# TJA1051T.net
KiCad netlist of a schematic drawn in Altium Designer
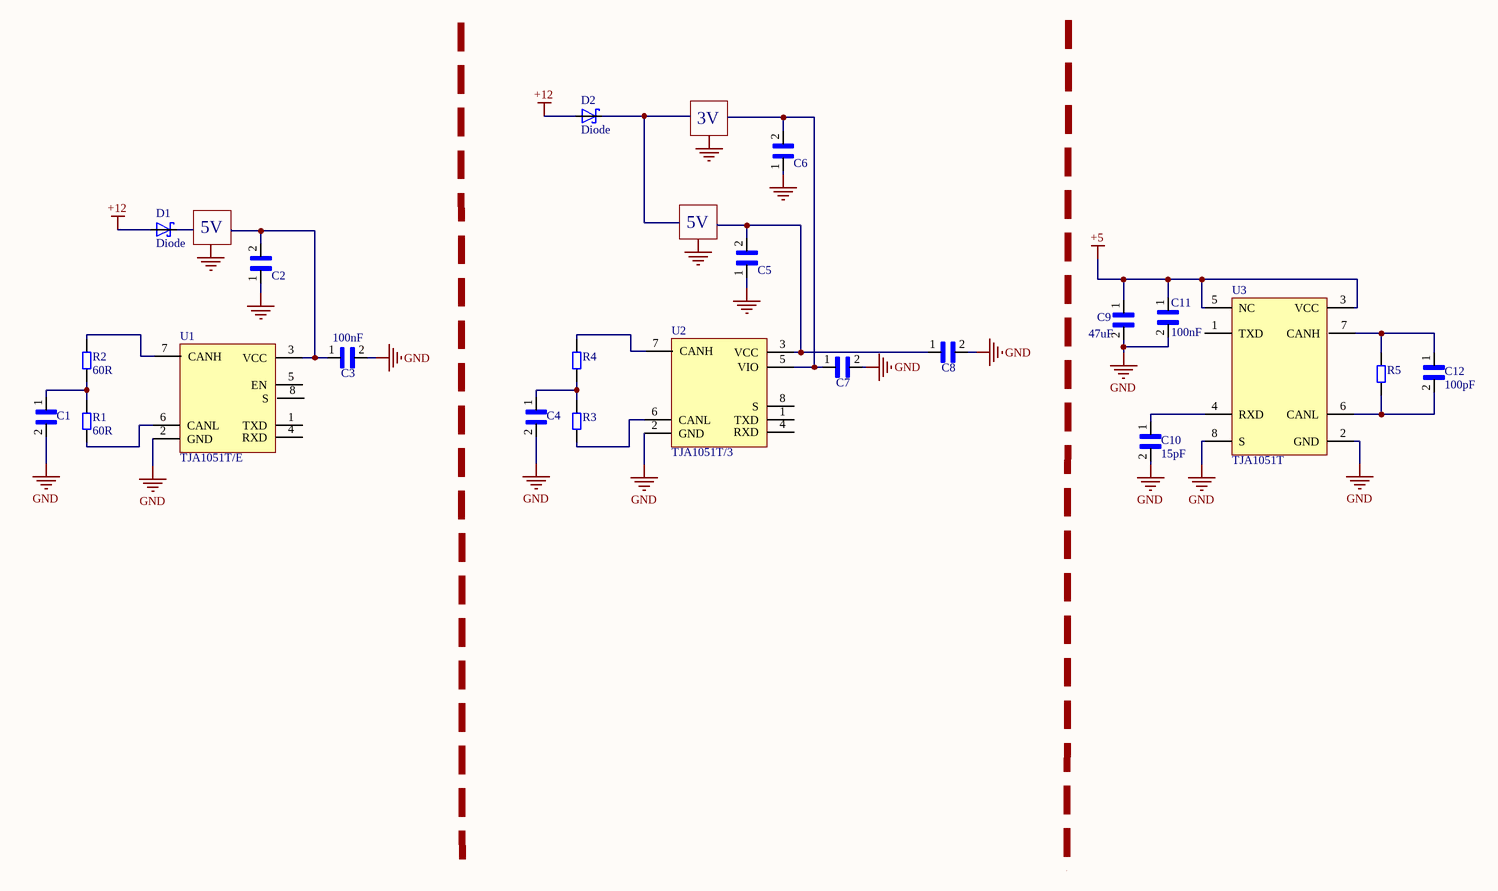
[diagram p0: TJA1051T.SchDoc]

(export (version "E")
  (design (tool "Eeschema 10.0.6"))
  (components
    (comp (ref "C1")
      (value "CAP-0805-NP0-10nF")
      (footprint "CAP-0805-NP0")
      (description "Cap Ceramic 0.01uF 50V C0G 5% Pad SMD 0805 125°C T/R")
      (fields
        (field (name "MANUFACTURER") "Yageo")
        (field (name "MANUFACTURER PART NUMBER") "CC0805JKNPO9BN103")
      )
      (libsource (lib "Schlib2") (part "CAP-0805-NP0-10nF"))
    )
    (comp (ref "C2")
      (value "CAP-0805-NP0-10nF")
      (footprint "CAP-0805-NP0")
      (description "Cap Ceramic 0.01uF 50V C0G 5% Pad SMD 0805 125°C T/R")
      (fields
        (field (name "MANUFACTURER") "Yageo")
        (field (name "MANUFACTURER PART NUMBER") "CC0805JKNPO9BN103")
      )
      (libsource (lib "") (part "CAP-0805-NP0-10nF_2"))
    )
    (comp (ref "C3")
      (value "100nF")
      (footprint "CAP-0805-NP0")
      (description "Cap Ceramic 0.01uF 50V C0G 5% Pad SMD 0805 125°C T/R")
      (fields
        (field (name "MANUFACTURER") "Yageo")
        (field (name "MANUFACTURER PART NUMBER") "CC0805JKNPO9BN103")
      )
      (libsource (lib "") (part "CAP-0805-NP0-10nF_1"))
    )
    (comp (ref "C4")
      (value "CAP-0805-NP0-10nF")
      (footprint "CAP-0805-NP0")
      (description "Cap Ceramic 0.01uF 50V C0G 5% Pad SMD 0805 125°C T/R")
      (fields
        (field (name "MANUFACTURER") "Yageo")
        (field (name "MANUFACTURER PART NUMBER") "CC0805JKNPO9BN103")
      )
      (libsource (lib "Schlib2") (part "CAP-0805-NP0-10nF"))
    )
    (comp (ref "C5")
      (value "CAP-0805-NP0-10nF")
      (footprint "CAP-0805-NP0")
      (description "Cap Ceramic 0.01uF 50V C0G 5% Pad SMD 0805 125°C T/R")
      (fields
        (field (name "MANUFACTURER") "Yageo")
        (field (name "MANUFACTURER PART NUMBER") "CC0805JKNPO9BN103")
      )
      (libsource (lib "") (part "CAP-0805-NP0-10nF_2"))
    )
    (comp (ref "C6")
      (value "CAP-0805-NP0-10nF")
      (footprint "CAP-0805-NP0")
      (description "Cap Ceramic 0.01uF 50V C0G 5% Pad SMD 0805 125°C T/R")
      (fields
        (field (name "MANUFACTURER") "Yageo")
        (field (name "MANUFACTURER PART NUMBER") "CC0805JKNPO9BN103")
      )
      (libsource (lib "") (part "CAP-0805-NP0-10nF_2"))
    )
    (comp (ref "C7")
      (value "CAP-0805-NP0-10nF")
      (footprint "CAP-0805-NP0")
      (description "Cap Ceramic 0.01uF 50V C0G 5% Pad SMD 0805 125°C T/R")
      (fields
        (field (name "MANUFACTURER") "Yageo")
        (field (name "MANUFACTURER PART NUMBER") "CC0805JKNPO9BN103")
      )
      (libsource (lib "") (part "CAP-0805-NP0-10nF_1"))
    )
    (comp (ref "C8")
      (value "CAP-0805-NP0-10nF")
      (footprint "CAP-0805-NP0")
      (description "Cap Ceramic 0.01uF 50V C0G 5% Pad SMD 0805 125°C T/R")
      (fields
        (field (name "MANUFACTURER") "Yageo")
        (field (name "MANUFACTURER PART NUMBER") "CC0805JKNPO9BN103")
      )
      (libsource (lib "") (part "CAP-0805-NP0-10nF_1"))
    )
    (comp (ref "C9")
      (value "47uF")
      (footprint "CAP-0805-NP0")
      (description "Cap Ceramic 0.01uF 50V C0G 5% Pad SMD 0805 125°C T/R")
      (fields
        (field (name "MANUFACTURER") "Yageo")
        (field (name "MANUFACTURER PART NUMBER") "CC0805JKNPO9BN103")
      )
      (libsource (lib "Schlib2") (part "CAP-0805-NP0-10nF"))
    )
    (comp (ref "C10")
      (value "15pF")
      (footprint "CAP-0805-NP0")
      (description "Cap Ceramic 0.01uF 50V C0G 5% Pad SMD 0805 125°C T/R")
      (fields
        (field (name "MANUFACTURER") "Yageo")
        (field (name "MANUFACTURER PART NUMBER") "CC0805JKNPO9BN103")
      )
      (libsource (lib "Schlib2") (part "CAP-0805-NP0-10nF"))
    )
    (comp (ref "C11")
      (value "100nF")
      (footprint "CAP-0805-NP0")
      (description "Cap Ceramic 0.01uF 50V C0G 5% Pad SMD 0805 125°C T/R")
      (fields
        (field (name "MANUFACTURER") "Yageo")
        (field (name "MANUFACTURER PART NUMBER") "CC0805JKNPO9BN103")
      )
      (libsource (lib "Schlib2") (part "CAP-0805-NP0-10nF"))
    )
    (comp (ref "C12")
      (value "100pF")
      (footprint "CAP-0805-NP0")
      (description "Cap Ceramic 0.01uF 50V C0G 5% Pad SMD 0805 125°C T/R")
      (fields
        (field (name "MANUFACTURER") "Yageo")
        (field (name "MANUFACTURER PART NUMBER") "CC0805JKNPO9BN103")
      )
      (libsource (lib "Schlib2") (part "CAP-0805-NP0-10nF"))
    )
    (comp (ref "D1") (value "Diode") (footprint "Diode") (libsource (lib "") (part "Diode_1")))
    (comp (ref "D2") (value "Diode") (footprint "Diode") (libsource (lib "Schlib1") (part "Diode")))
    (comp (ref "R1")
      (value "60R")
      (footprint "RES-0805")
      (description "Res SMD 0805 10K 1% 0.125W T.C.100PPM")
      (fields
        (field (name "MANUFACTURER") "Yageo")
        (field (name "MANUFACTURER PART NUMBER") "RC0805FR-0710KL")
      )
      (libsource (lib "Schlib2") (part "RES-0805-10k"))
    )
    (comp (ref "R2")
      (value "60R")
      (footprint "RES-0805")
      (description "Res SMD 0805 10K 1% 0.125W T.C.100PPM")
      (fields
        (field (name "MANUFACTURER") "Yageo")
        (field (name "MANUFACTURER PART NUMBER") "RC0805FR-0710KL")
      )
      (libsource (lib "Schlib2") (part "RES-0805-10k"))
    )
    (comp (ref "R3")
      (value "RES-0805-10k")
      (footprint "RES-0805")
      (description "Res SMD 0805 10K 1% 0.125W T.C.100PPM")
      (fields
        (field (name "MANUFACTURER") "Yageo")
        (field (name "MANUFACTURER PART NUMBER") "RC0805FR-0710KL")
      )
      (libsource (lib "Schlib2") (part "RES-0805-10k"))
    )
    (comp (ref "R4")
      (value "RES-0805-10k")
      (footprint "RES-0805")
      (description "Res SMD 0805 10K 1% 0.125W T.C.100PPM")
      (fields
        (field (name "MANUFACTURER") "Yageo")
        (field (name "MANUFACTURER PART NUMBER") "RC0805FR-0710KL")
      )
      (libsource (lib "Schlib2") (part "RES-0805-10k"))
    )
    (comp (ref "R5")
      (value "120R")
      (footprint "RES-0805")
      (description "Res SMD 0805 10K 1% 0.125W T.C.100PPM")
      (fields
        (field (name "MANUFACTURER") "Yageo")
        (field (name "MANUFACTURER PART NUMBER") "RC0805FR-0710KL")
      )
      (libsource (lib "Schlib2") (part "RES-0805-10k"))
    )
    (comp (ref "U1")
      (value "TJA1051T/E")
      (footprint "TJA1051T")
      (description "TJA1051 Series 5.5 V Surface Mount High-Speed CAN Transceiver - SOIC-8")
      (fields
        (field (name "MANUFACTURER") "NXP Semiconductors")
        (field (name "MANUFACTURER PART NUMBER") "TJA1051T/E,118")
      )
      (libsource (lib "Schlib1") (part "TJA1051T/E"))
    )
    (comp (ref "U2")
      (value "TJA1051T/3")
      (footprint "TJA1051T")
      (description "TJA1051 Single 5 V 1 MBd Surface Mount High Speed CAN Transceiver - HVSON-8")
      (fields
        (field (name "MANUFACTURER") "NXP Semiconductors")
        (field (name "MANUFACTURER PART NUMBER") "TJA1051TK/3/1J")
      )
      (libsource (lib "Schlib2") (part "TJA1051T/3"))
    )
    (comp (ref "U3")
      (value "TJA1051T")
      (footprint "TJA1051T")
      (description "CAN 1Mbps Normal/Silent 5V 8-Pin SO Tube")
      (fields (field (name "MANUFACTURER") "NXP Semiconductors"))
      (libsource (lib "Schlib2") (part "TJA1051T"))
    )
  )
  (nets
    (net (code "1") (name "+5") (class "Default")
      (node (ref "C11") (pin "1") (pinfunction "1_1") (pintype "passive"))
      (node (ref "C9") (pin "1") (pinfunction "1_1") (pintype "passive"))
      (node (ref "U3") (pin "3") (pinfunction "VCC_3") (pintype "passive"))
      (node (ref "U3") (pin "5") (pinfunction "NC_5") (pintype "power_in"))
    )
    (net (code "2") (name "+12") (class "Default")
      (node (ref "D1") (pin "1") (pintype "passive"))
      (node (ref "D2") (pin "2") (pintype "passive"))
    )
    (net (code "3") (name "GND") (class "Default")
      (node (ref "C1") (pin "2") (pinfunction "2_2") (pintype "passive"))
      (node (ref "C10") (pin "2") (pinfunction "2_2") (pintype "passive"))
      (node (ref "C11") (pin "2") (pinfunction "2_2") (pintype "passive"))
      (node (ref "C2") (pin "1") (pinfunction "1_1") (pintype "passive"))
      (node (ref "C3") (pin "2") (pinfunction "2_2") (pintype "passive"))
      (node (ref "C4") (pin "2") (pinfunction "2_2") (pintype "passive"))
      (node (ref "C5") (pin "1") (pinfunction "1_1") (pintype "passive"))
      (node (ref "C6") (pin "1") (pinfunction "1_1") (pintype "passive"))
      (node (ref "C7") (pin "2") (pinfunction "2_2") (pintype "passive"))
      (node (ref "C8") (pin "2") (pinfunction "2_2") (pintype "passive"))
      (node (ref "C9") (pin "2") (pinfunction "2_2") (pintype "passive"))
      (node (ref "U1") (pin "2") (pinfunction "GND_2") (pintype "passive"))
      (node (ref "U2") (pin "2") (pinfunction "GND_2") (pintype "passive"))
      (node (ref "U3") (pin "2") (pinfunction "GND_2") (pintype "passive"))
      (node (ref "U3") (pin "8") (pinfunction "S_8") (pintype "passive"))
    )
    (net (code "4") (name "Net-(C1-Pad1)") (class "Default")
      (node (ref "C1") (pin "1") (pinfunction "1_1") (pintype "passive"))
      (node (ref "R1") (pin "2") (pinfunction "2_2") (pintype "passive"))
      (node (ref "R2") (pin "1") (pinfunction "1_1") (pintype "passive"))
    )
    (net (code "5") (name "Net-(C4-Pad1)") (class "Default")
      (node (ref "C4") (pin "1") (pinfunction "1_1") (pintype "passive"))
      (node (ref "R3") (pin "2") (pinfunction "2_2") (pintype "passive"))
      (node (ref "R4") (pin "1") (pinfunction "1_1") (pintype "passive"))
    )
    (net (code "6") (name "Net-(U1-CANH)") (class "Default")
      (node (ref "R2") (pin "2") (pinfunction "2_2") (pintype "passive"))
      (node (ref "U1") (pin "7") (pinfunction "CANH_7") (pintype "passive"))
    )
    (net (code "7") (name "Net-(U1-CANL)") (class "Default")
      (node (ref "R1") (pin "1") (pinfunction "1_1") (pintype "passive"))
      (node (ref "U1") (pin "6") (pinfunction "CANL_6") (pintype "passive"))
    )
    (net (code "8") (name "Net-(U1-VCC)") (class "Default")
      (node (ref "C2") (pin "2") (pinfunction "2_2") (pintype "passive"))
      (node (ref "C3") (pin "1") (pinfunction "1_1") (pintype "passive"))
      (node (ref "U1") (pin "3") (pinfunction "VCC_3") (pintype "passive"))
    )
    (net (code "9") (name "Net-(U2-CANH)") (class "Default")
      (node (ref "R4") (pin "2") (pinfunction "2_2") (pintype "passive"))
      (node (ref "U2") (pin "7") (pinfunction "CANH_7") (pintype "passive"))
    )
    (net (code "10") (name "Net-(U2-CANL)") (class "Default")
      (node (ref "R3") (pin "1") (pinfunction "1_1") (pintype "passive"))
      (node (ref "U2") (pin "6") (pinfunction "CANL_6") (pintype "passive"))
    )
    (net (code "11") (name "Net-(U2-VCC)") (class "Default")
      (node (ref "C5") (pin "2") (pinfunction "2_2") (pintype "passive"))
      (node (ref "C8") (pin "1") (pinfunction "1_1") (pintype "passive"))
      (node (ref "U2") (pin "3") (pinfunction "VCC_3") (pintype "passive"))
    )
    (net (code "12") (name "Net-(U2-VIO)") (class "Default")
      (node (ref "C6") (pin "2") (pinfunction "2_2") (pintype "passive"))
      (node (ref "C7") (pin "1") (pinfunction "1_1") (pintype "passive"))
      (node (ref "U2") (pin "5") (pinfunction "VIO_5") (pintype "power_in"))
    )
    (net (code "13") (name "Net-(U3-CANH)") (class "Default")
      (node (ref "C12") (pin "1") (pinfunction "1_1") (pintype "passive"))
      (node (ref "R5") (pin "2") (pinfunction "2_2") (pintype "passive"))
      (node (ref "U3") (pin "7") (pinfunction "CANH_7") (pintype "passive"))
    )
    (net (code "14") (name "Net-(U3-CANL)") (class "Default")
      (node (ref "C12") (pin "2") (pinfunction "2_2") (pintype "passive"))
      (node (ref "R5") (pin "1") (pinfunction "1_1") (pintype "passive"))
      (node (ref "U3") (pin "6") (pinfunction "CANL_6") (pintype "passive"))
    )
    (net (code "15") (name "Net-(U3-RXD)") (class "Default")
      (node (ref "C10") (pin "1") (pinfunction "1_1") (pintype "passive"))
      (node (ref "U3") (pin "4") (pinfunction "RXD_4") (pintype "passive"))
    )
    (net (code "16") (name "unconnected-(D1-Pad2)") (class "Default")
      (node (ref "D1") (pin "2") (pintype "passive"))
    )
    (net (code "17") (name "unconnected-(D2-Pad1)") (class "Default")
      (node (ref "D2") (pin "1") (pintype "passive"))
    )
    (net (code "18") (name "unconnected-(U1-EN-Pad5)") (class "Default")
      (node (ref "U1") (pin "5") (pinfunction "EN_5") (pintype "power_in"))
    )
    (net (code "19") (name "unconnected-(U1-RXD-Pad4)") (class "Default")
      (node (ref "U1") (pin "4") (pinfunction "RXD_4") (pintype "passive"))
    )
    (net (code "20") (name "unconnected-(U1-S-Pad8)") (class "Default")
      (node (ref "U1") (pin "8") (pinfunction "S_8") (pintype "passive"))
    )
    (net (code "21") (name "unconnected-(U1-TXD-Pad1)") (class "Default")
      (node (ref "U1") (pin "1") (pinfunction "TXD_1") (pintype "passive"))
    )
    (net (code "22") (name "unconnected-(U2-RXD-Pad4)") (class "Default")
      (node (ref "U2") (pin "4") (pinfunction "RXD_4") (pintype "passive"))
    )
    (net (code "23") (name "unconnected-(U2-S-Pad8)") (class "Default")
      (node (ref "U2") (pin "8") (pinfunction "S_8") (pintype "passive"))
    )
    (net (code "24") (name "unconnected-(U2-TXD-Pad1)") (class "Default")
      (node (ref "U2") (pin "1") (pinfunction "TXD_1") (pintype "passive"))
    )
    (net (code "25") (name "unconnected-(U3-TXD-Pad1)") (class "Default")
      (node (ref "U3") (pin "1") (pinfunction "TXD_1") (pintype "passive"))
    )
  )
)
